# Test.net
KiCad netlist of a schematic drawn in Altium Designer
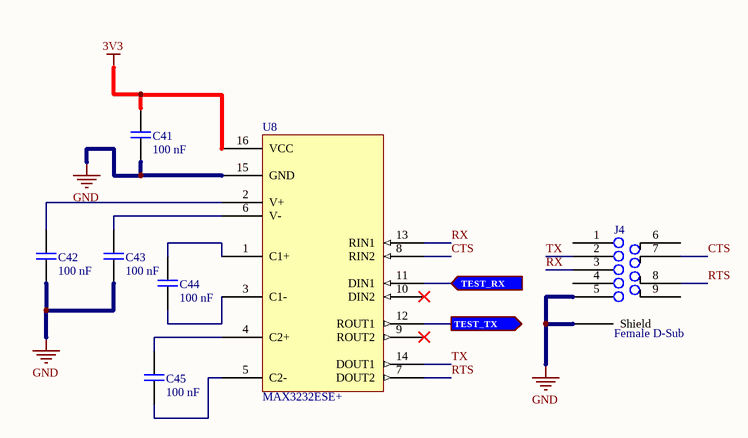
[diagram p0: Test.SchDoc]

(export (version "E")
  (design (tool "Eeschema 10.0.6"))
  (components
    (comp (ref "C41")
      (value "100 nF")
      (footprint "MergenElektronik_Capacitors_Ceramics_SMDs_0603_M_NS")
      (description "Mergen Elektronik - Capacitors - Ceramics - SMDs - 0603 - 100 nF - 100V")
      (fields (field (name "MANUFACTURER") "Samsung Electro-Mechanics") (field (name "TOLERANCE") "±10%"))
      (libsource (lib "MergenElektronik_Capacitors_Ceramics_SMDs") (part "MergenElektronik_Capacitors_Ceramic_SMDs_100nF_100V"))
    )
    (comp (ref "C42")
      (value "100 nF")
      (footprint "MergenElektronik_Capacitors_Ceramics_SMDs_0603_M_NS")
      (description "Mergen Elektronik - Capacitors - Ceramics - SMDs - 0603 - 100 nF - 100V")
      (fields (field (name "MANUFACTURER") "Samsung Electro-Mechanics") (field (name "TOLERANCE") "±10%"))
      (libsource (lib "MergenElektronik_Capacitors_Ceramics_SMDs") (part "MergenElektronik_Capacitors_Ceramic_SMDs_100nF_100V"))
    )
    (comp (ref "C43")
      (value "100 nF")
      (footprint "MergenElektronik_Capacitors_Ceramics_SMDs_0603_M_NS")
      (description "Mergen Elektronik - Capacitors - Ceramics - SMDs - 0603 - 100 nF - 100V")
      (fields (field (name "MANUFACTURER") "Samsung Electro-Mechanics") (field (name "TOLERANCE") "±10%"))
      (libsource (lib "MergenElektronik_Capacitors_Ceramics_SMDs") (part "MergenElektronik_Capacitors_Ceramic_SMDs_100nF_100V"))
    )
    (comp (ref "C44")
      (value "100 nF")
      (footprint "MergenElektronik_Capacitors_Ceramics_SMDs_0603_M_NS")
      (description "Mergen Elektronik - Capacitors - Ceramics - SMDs - 0603 - 100 nF - 100V")
      (fields (field (name "MANUFACTURER") "Samsung Electro-Mechanics") (field (name "TOLERANCE") "±10%"))
      (libsource (lib "MergenElektronik_Capacitors_Ceramics_SMDs") (part "MergenElektronik_Capacitors_Ceramic_SMDs_100nF_100V"))
    )
    (comp (ref "C45")
      (value "100 nF")
      (footprint "MergenElektronik_Capacitors_Ceramics_SMDs_0603_M_NS")
      (description "Mergen Elektronik - Capacitors - Ceramics - SMDs - 0603 - 100 nF - 100V")
      (fields (field (name "MANUFACTURER") "Samsung Electro-Mechanics") (field (name "TOLERANCE") "±10%"))
      (libsource (lib "MergenElektronik_Capacitors_Ceramics_SMDs") (part "MergenElektronik_Capacitors_Ceramic_SMDs_100nF_100V"))
    )
    (comp (ref "J4")
      (value "Female D-Sub")
      (footprint "MergenElektronik_Libraries_Connectors_D-Sub_9Position")
      (description "Mergen Elektronik - Connectors - D-Sub - Female 9 Position")
      (fields (field (name "MANUFACTURER") "Assmann WSW Components"))
      (libsource (lib "MergenElektronik_Connectors_D-Sub") (part "MergenElekttronik_Connectors_D-Sub_Female_9Position"))
    )
    (comp (ref "U8")
      (value "MAX3232ESE+")
      (footprint "MergenElektronik_Interfaces_RS232s_SOIC-16")
      (description "Mergen Elektronik - Interfaces - RS232s - MAX3232ESE+")
      (fields (field (name "MANUFACTURER") "Analog Devices Inc./Maxim Integrated"))
      (libsource (lib "MergenElektronik_Interfaces_RS232s") (part "MergenElektronik_Interfaces_RS232s_MAX3232ESE+"))
    )
  )
  (nets
    (net (code "1") (name "/CTS") (class "Default")
      (node (ref "J4") (pin "7") (pinfunction "7_7") (pintype "passive"))
      (node (ref "U8") (pin "8") (pinfunction "RIN2_8") (pintype "input"))
    )
    (net (code "2") (name "/RTS") (class "Default")
      (node (ref "J4") (pin "8") (pinfunction "8_8") (pintype "passive"))
      (node (ref "U8") (pin "7") (pinfunction "DOUT2_7") (pintype "output"))
    )
    (net (code "3") (name "/RX") (class "Default")
      (node (ref "J4") (pin "3") (pinfunction "3_3") (pintype "passive"))
      (node (ref "U8") (pin "13") (pinfunction "RIN1_13") (pintype "input"))
    )
    (net (code "4") (name "/TEST_RX") (class "Default")
      (node (ref "U8") (pin "11") (pinfunction "DIN1_11") (pintype "input"))
    )
    (net (code "5") (name "/TEST_TX") (class "Default")
      (node (ref "U8") (pin "12") (pinfunction "ROUT1_12") (pintype "output"))
    )
    (net (code "6") (name "/TX") (class "Default")
      (node (ref "J4") (pin "2") (pinfunction "2_2") (pintype "passive"))
      (node (ref "U8") (pin "14") (pinfunction "DOUT1_14") (pintype "output"))
    )
    (net (code "7") (name "3V3") (class "Default")
      (node (ref "C41") (pin "1") (pinfunction "1_1") (pintype "passive"))
      (node (ref "U8") (pin "16") (pinfunction "VCC_16") (pintype "power_in"))
    )
    (net (code "8") (name "GND") (class "Default")
      (node (ref "C41") (pin "2") (pinfunction "2_2") (pintype "passive"))
      (node (ref "C42") (pin "2") (pinfunction "2_2") (pintype "passive"))
      (node (ref "C43") (pin "2") (pinfunction "2_2") (pintype "passive"))
      (node (ref "J4") (pin "5") (pinfunction "5_5") (pintype "passive"))
      (node (ref "J4") (pin "Shield") (pinfunction "Shield_Shield") (pintype "passive"))
      (node (ref "U8") (pin "15") (pinfunction "GND_15") (pintype "power_in"))
    )
    (net (code "9") (name "Net-(U8-C1+)") (class "Default")
      (node (ref "C44") (pin "1") (pinfunction "1_1") (pintype "passive"))
      (node (ref "U8") (pin "1") (pinfunction "C1+_1") (pintype "power_in"))
    )
    (net (code "10") (name "Net-(U8-C1-)") (class "Default")
      (node (ref "C44") (pin "2") (pinfunction "2_2") (pintype "passive"))
      (node (ref "U8") (pin "3") (pinfunction "C1-_3") (pintype "power_in"))
    )
    (net (code "11") (name "Net-(U8-C2+)") (class "Default")
      (node (ref "C45") (pin "1") (pinfunction "1_1") (pintype "passive"))
      (node (ref "U8") (pin "4") (pinfunction "C2+_4") (pintype "power_in"))
    )
    (net (code "12") (name "Net-(U8-C2-)") (class "Default")
      (node (ref "C45") (pin "2") (pinfunction "2_2") (pintype "passive"))
      (node (ref "U8") (pin "5") (pinfunction "C2-_5") (pintype "power_in"))
    )
    (net (code "13") (name "Net-(U8-V+)") (class "Default")
      (node (ref "C42") (pin "1") (pinfunction "1_1") (pintype "passive"))
      (node (ref "U8") (pin "2") (pinfunction "V+_2") (pintype "power_in"))
    )
    (net (code "14") (name "Net-(U8-V-)") (class "Default")
      (node (ref "C43") (pin "1") (pinfunction "1_1") (pintype "passive"))
      (node (ref "U8") (pin "6") (pinfunction "V-_6") (pintype "power_in"))
    )
    (net (code "15") (name "unconnected-(J4-Pad1)") (class "Default")
      (node (ref "J4") (pin "1") (pinfunction "1_1") (pintype "passive"))
    )
    (net (code "16") (name "unconnected-(J4-Pad4)") (class "Default")
      (node (ref "J4") (pin "4") (pinfunction "4_4") (pintype "passive"))
    )
    (net (code "17") (name "unconnected-(J4-Pad6)") (class "Default")
      (node (ref "J4") (pin "6") (pinfunction "6_6") (pintype "passive"))
    )
    (net (code "18") (name "unconnected-(J4-Pad9)") (class "Default")
      (node (ref "J4") (pin "9") (pinfunction "9_9") (pintype "passive"))
    )
    (net (code "19") (name "unconnected-(U8-DIN2-Pad10)") (class "Default")
      (node (ref "U8") (pin "10") (pinfunction "DIN2_10") (pintype "input+no_connect"))
    )
    (net (code "20") (name "unconnected-(U8-ROUT2-Pad9)") (class "Default")
      (node (ref "U8") (pin "9") (pinfunction "ROUT2_9") (pintype "output+no_connect"))
    )
  )
)
